# xbee.net
KiCad netlist of a schematic drawn in EAGLE
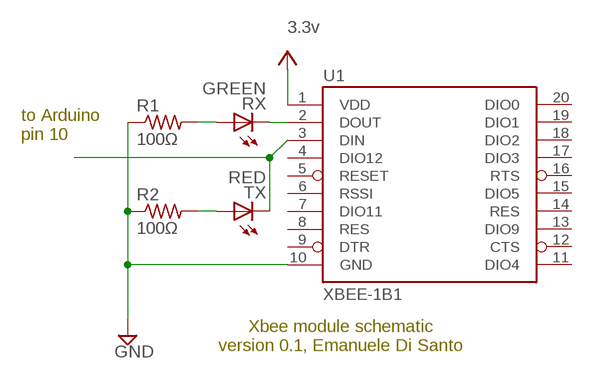
[diagram p0: schematic, sheet 1]

(export (version "E")
  (design (tool "Eeschema 10.0.6"))
  (components
    (comp (ref "R1")
      (value "100Ω")
      (footprint "eagle-import:R3216")
      (libsource (lib "eagle-import") (part "R-US_R3216"))
    )
    (comp (ref "R2")
      (value "100Ω")
      (footprint "eagle-import:R3216")
      (libsource (lib "eagle-import") (part "R-US_R3216"))
    )
    (comp (ref "RX")
      (value "GREEN")
      (footprint "eagle-import:CHIP-LED0805")
      (libsource (lib "eagle-import") (part "LEDCHIP-LED0805"))
    )
    (comp (ref "TX")
      (value "RED")
      (footprint "eagle-import:CHIP-LED0805")
      (libsource (lib "eagle-import") (part "LEDCHIP-LED0805"))
    )
    (comp (ref "U1")
      (value "XBEE-1B1")
      (footprint "eagle-import:XBEE-1")
      (libsource (lib "eagle-import") (part "XBEE-1B1"))
    )
  )
  (nets
    (net (code "1") (name "3.3v") (class "Default")
      (node (ref "U1") (pin "1") (pinfunction "VDD_1") (pintype "power_in"))
    )
    (net (code "2") (name "GND") (class "Default")
      (node (ref "R1") (pin "1") (pinfunction "1_1") (pintype "passive"))
      (node (ref "R2") (pin "1") (pinfunction "1_1") (pintype "passive"))
      (node (ref "U1") (pin "10") (pinfunction "GND_10") (pintype "power_in"))
    )
    (net (code "3") (name "Net-(R1-Pad2)") (class "Default")
      (node (ref "R1") (pin "2") (pinfunction "2_2") (pintype "passive"))
      (node (ref "RX") (pin "A") (pinfunction "A_A") (pintype "passive"))
    )
    (net (code "4") (name "Net-(R2-Pad2)") (class "Default")
      (node (ref "R2") (pin "2") (pinfunction "2_2") (pintype "passive"))
      (node (ref "TX") (pin "A") (pinfunction "A_A") (pintype "passive"))
    )
    (net (code "5") (name "Net-(U1-DIN)") (class "Default")
      (node (ref "TX") (pin "C") (pinfunction "C_C") (pintype "passive"))
      (node (ref "U1") (pin "3") (pinfunction "DIN_3") (pintype "input"))
    )
    (net (code "6") (name "Net-(U1-DOUT)") (class "Default")
      (node (ref "RX") (pin "C") (pinfunction "C_C") (pintype "passive"))
      (node (ref "U1") (pin "2") (pinfunction "DOUT_2") (pintype "output"))
    )
    (net (code "7") (name "unconnected-(U1-CTS-Pad12)") (class "Default")
      (node (ref "U1") (pin "12") (pinfunction "CTS_12") (pintype "output"))
    )
    (net (code "8") (name "unconnected-(U1-DIO0-Pad20)") (class "Default")
      (node (ref "U1") (pin "20") (pinfunction "DIO0_20") (pintype "bidirectional"))
    )
    (net (code "9") (name "unconnected-(U1-DIO1-Pad19)") (class "Default")
      (node (ref "U1") (pin "19") (pinfunction "DIO1_19") (pintype "bidirectional"))
    )
    (net (code "10") (name "unconnected-(U1-DIO2-Pad18)") (class "Default")
      (node (ref "U1") (pin "18") (pinfunction "DIO2_18") (pintype "bidirectional"))
    )
    (net (code "11") (name "unconnected-(U1-DIO3-Pad17)") (class "Default")
      (node (ref "U1") (pin "17") (pinfunction "DIO3_17") (pintype "bidirectional"))
    )
    (net (code "12") (name "unconnected-(U1-DIO4-Pad11)") (class "Default")
      (node (ref "U1") (pin "11") (pinfunction "DIO4_11") (pintype "bidirectional"))
    )
    (net (code "13") (name "unconnected-(U1-DIO5-Pad15)") (class "Default")
      (node (ref "U1") (pin "15") (pinfunction "DIO5_15") (pintype "bidirectional"))
    )
    (net (code "14") (name "unconnected-(U1-DIO9-Pad13)") (class "Default")
      (node (ref "U1") (pin "13") (pinfunction "DIO9_13") (pintype "bidirectional"))
    )
    (net (code "15") (name "unconnected-(U1-DIO11-Pad7)") (class "Default")
      (node (ref "U1") (pin "7") (pinfunction "DIO11_7") (pintype "bidirectional"))
    )
    (net (code "16") (name "unconnected-(U1-DIO12-Pad4)") (class "Default")
      (node (ref "U1") (pin "4") (pinfunction "DIO12_4") (pintype "bidirectional"))
    )
    (net (code "17") (name "unconnected-(U1-DTR-Pad9)") (class "Default")
      (node (ref "U1") (pin "9") (pinfunction "DTR_9") (pintype "bidirectional"))
    )
    (net (code "18") (name "unconnected-(U1-RES-Pad8)") (class "Default")
      (node (ref "U1") (pin "8") (pinfunction "RES_8") (pintype "bidirectional"))
    )
    (net (code "19") (name "unconnected-(U1-RES-Pad14)") (class "Default")
      (node (ref "U1") (pin "14") (pinfunction "RES_14") (pintype "bidirectional"))
    )
    (net (code "20") (name "unconnected-(U1-RESET-Pad5)") (class "Default")
      (node (ref "U1") (pin "5") (pinfunction "RESET_5") (pintype "input"))
    )
    (net (code "21") (name "unconnected-(U1-RSSI-Pad6)") (class "Default")
      (node (ref "U1") (pin "6") (pinfunction "RSSI_6") (pintype "bidirectional"))
    )
    (net (code "22") (name "unconnected-(U1-RTS-Pad16)") (class "Default")
      (node (ref "U1") (pin "16") (pinfunction "RTS_16") (pintype "input"))
    )
  )
)
